# CSR8635-V1_2.net
KiCad netlist of a schematic drawn in EAGLE
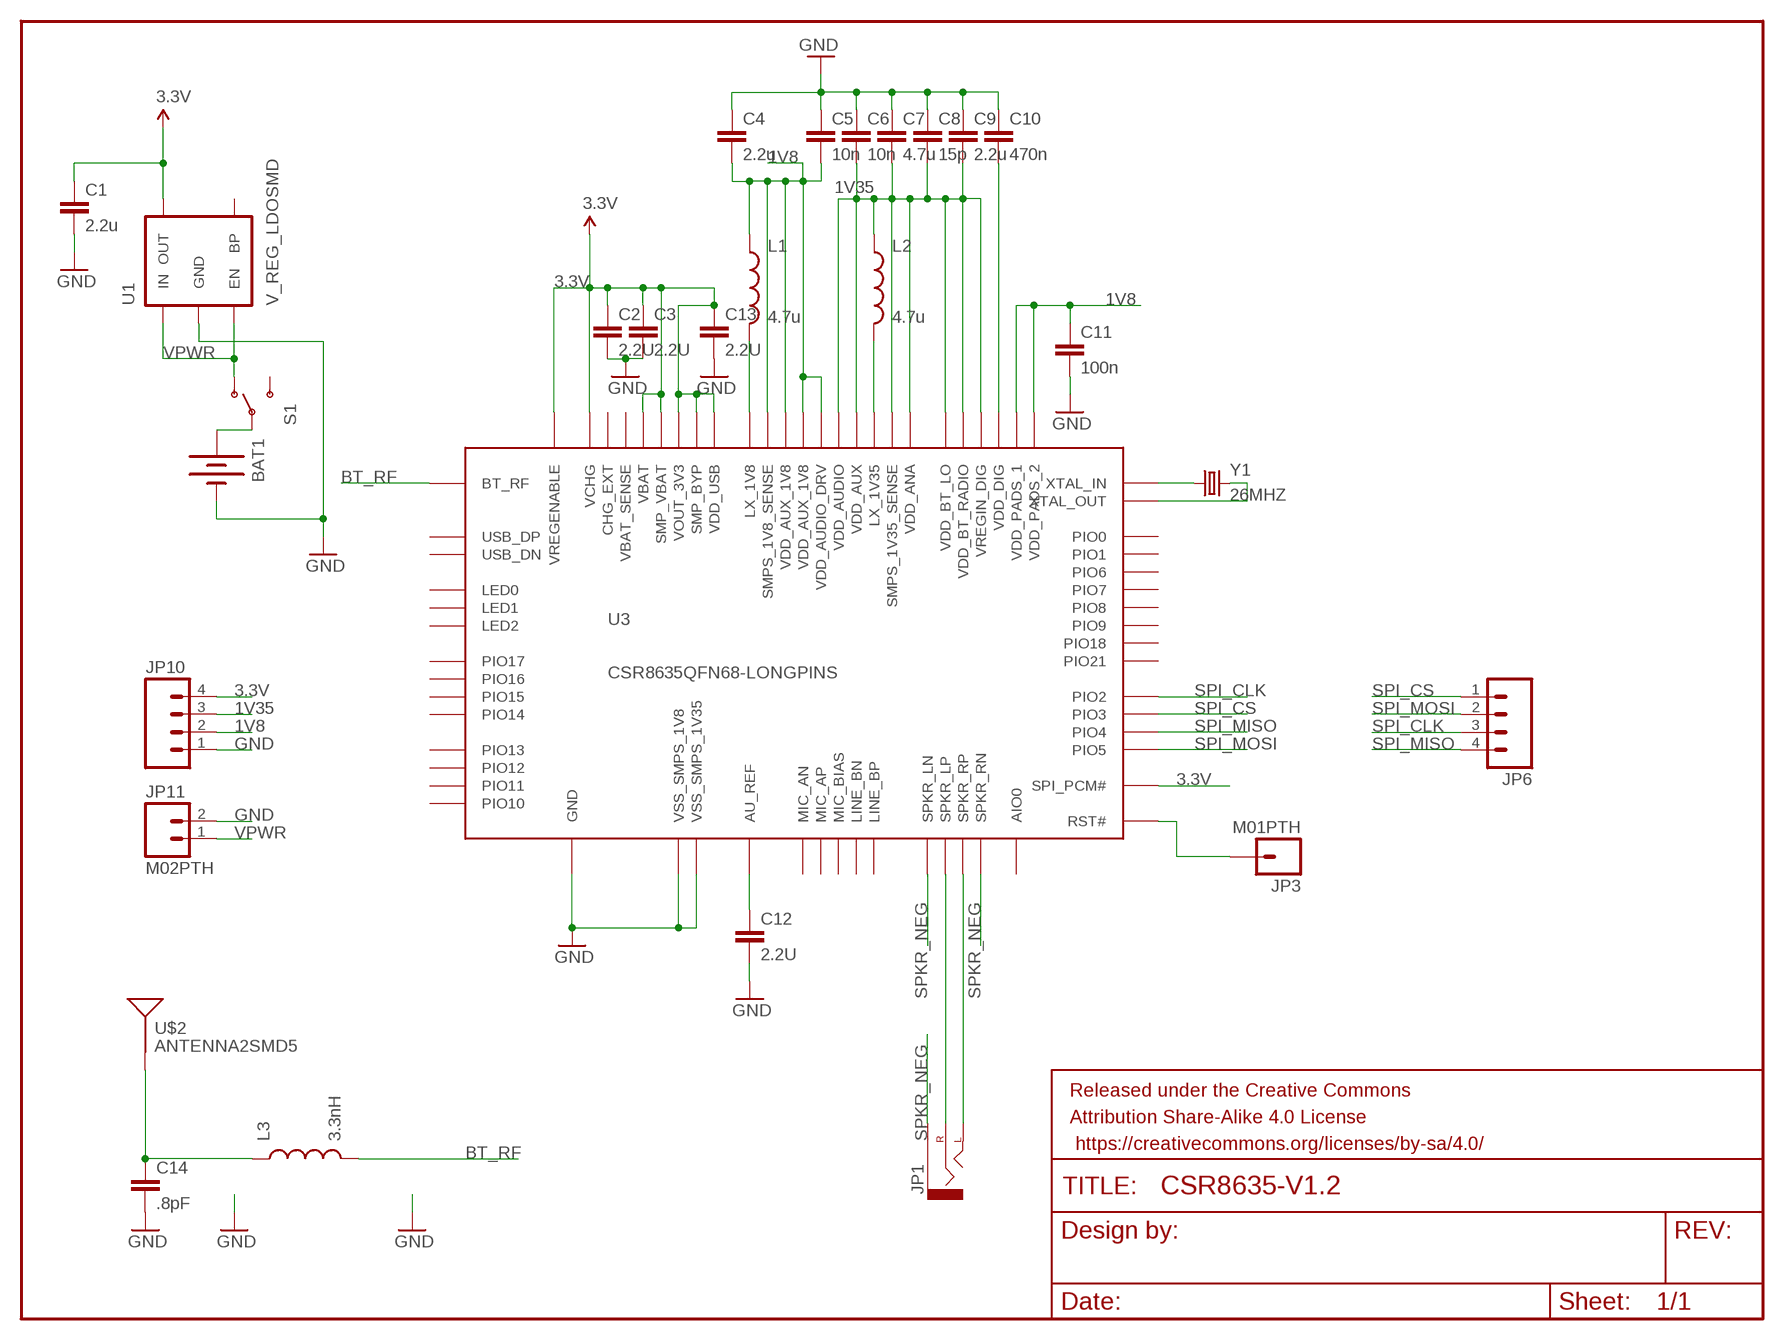
[diagram p0: schematic, sheet 1]

(export (version "E")
  (design (tool "Eeschema 10.0.6"))
  (components
    (comp (ref "BAT1")
      (value "BATTERY9V")
      (footprint "eagle-import:BATTCON_9V")
      (libsource (lib "eagle-import") (part "BATTERY9V"))
    )
    (comp (ref "C1")
      (value "2.2u")
      (footprint "eagle-import:0603-CAP")
      (libsource (lib "eagle-import") (part "CAP0603-CAP"))
    )
    (comp (ref "C2")
      (value "2.2U")
      (footprint "eagle-import:0603-CAP")
      (libsource (lib "eagle-import") (part "CAP0603-CAP"))
    )
    (comp (ref "C3")
      (value "2.2U")
      (footprint "eagle-import:0603-CAP")
      (libsource (lib "eagle-import") (part "CAP0603-CAP"))
    )
    (comp (ref "C4")
      (value "2.2u")
      (footprint "eagle-import:0603-CAP")
      (libsource (lib "eagle-import") (part "CAP0603-CAP"))
    )
    (comp (ref "C5")
      (value "10n")
      (footprint "eagle-import:0603-CAP")
      (libsource (lib "eagle-import") (part "CAP0603-CAP"))
    )
    (comp (ref "C6")
      (value "10n")
      (footprint "eagle-import:0603-CAP")
      (libsource (lib "eagle-import") (part "CAP0603-CAP"))
    )
    (comp (ref "C7")
      (value "4.7u")
      (footprint "eagle-import:0603-CAP")
      (libsource (lib "eagle-import") (part "CAP0603-CAP"))
    )
    (comp (ref "C8")
      (value "15p")
      (footprint "eagle-import:0603-CAP")
      (libsource (lib "eagle-import") (part "CAP0603-CAP"))
    )
    (comp (ref "C9")
      (value "2.2u")
      (footprint "eagle-import:0603-CAP")
      (libsource (lib "eagle-import") (part "CAP0603-CAP"))
    )
    (comp (ref "C10")
      (value "470n")
      (footprint "eagle-import:0603-CAP")
      (libsource (lib "eagle-import") (part "CAP0603-CAP"))
    )
    (comp (ref "C11")
      (value "100n")
      (footprint "eagle-import:0603-CAP")
      (libsource (lib "eagle-import") (part "CAP0603-CAP"))
    )
    (comp (ref "C12")
      (value "2.2U")
      (footprint "eagle-import:0603-CAP")
      (libsource (lib "eagle-import") (part "CAP0603-CAP"))
    )
    (comp (ref "C13")
      (value "2.2U")
      (footprint "eagle-import:0603-CAP")
      (libsource (lib "eagle-import") (part "CAP0603-CAP"))
    )
    (comp (ref "C14")
      (value ".8pF")
      (footprint "eagle-import:0603-CAP")
      (libsource (lib "eagle-import") (part "CAP0603-CAP"))
    )
    (comp (ref "FRAME1")
      (value "FRAME-LETTER")
      (footprint "eagle-import:CREATIVE_COMMONS")
      (libsource (lib "eagle-import") (part "FRAME-LETTER"))
    )
    (comp (ref "JP1")
      (value "AUDIO-JACKSMD2")
      (footprint "eagle-import:AUDIO-JACK-3.5MM-SMD")
      (libsource (lib "eagle-import") (part "AUDIO-JACKSMD2"))
    )
    (comp (ref "JP3")
      (value "M01PTH")
      (footprint "eagle-import:1X01")
      (libsource (lib "eagle-import") (part "M01PTH"))
    )
    (comp (ref "JP6")
      (value "M04PTH")
      (footprint "eagle-import:1X04")
      (libsource (lib "eagle-import") (part "M04PTH"))
    )
    (comp (ref "JP10")
      (value "M04PTH")
      (footprint "eagle-import:1X04")
      (libsource (lib "eagle-import") (part "M04PTH"))
    )
    (comp (ref "JP11")
      (value "M02PTH")
      (footprint "eagle-import:1X02")
      (libsource (lib "eagle-import") (part "M02PTH"))
    )
    (comp (ref "L1")
      (value "4.7u")
      (footprint "eagle-import:0805")
      (libsource (lib "eagle-import") (part "INDUCTOR0805"))
    )
    (comp (ref "L2")
      (value "4.7u")
      (footprint "eagle-import:0805")
      (libsource (lib "eagle-import") (part "INDUCTOR0805"))
    )
    (comp (ref "L3")
      (value "3.3nH")
      (footprint "eagle-import:0805")
      (libsource (lib "eagle-import") (part "INDUCTOR0805"))
    )
    (comp (ref "S1")
      (value "SWITCH-SPDTPTH")
      (footprint "eagle-import:SWITCH-SPDT")
      (libsource (lib "eagle-import") (part "SWITCH-SPDTPTH"))
    )
    (comp (ref "U$2")
      (value "ANTENNA2SMD5")
      (footprint "eagle-import:ANTENNA-CHIP5")
      (libsource (lib "eagle-import") (part "ANTENNA2SMD5"))
    )
    (comp (ref "U1")
      (value "V_REG_LDOSMD")
      (footprint "eagle-import:SOT23-5")
      (libsource (lib "eagle-import") (part "V_REG_LDOSMD"))
    )
    (comp (ref "U3")
      (value "CSR8635QFN68-LONGPINS")
      (footprint "eagle-import:QFN68")
      (libsource (lib "eagle-import") (part "CSR8635QFN68-LONGPINS"))
    )
    (comp (ref "Y1")
      (value "26MHZ")
      (footprint "eagle-import:HC49US")
      (libsource (lib "eagle-import") (part "CRYSTALHC49US"))
    )
  )
  (nets
    (net (code "1") (name "/1V8") (class "Default")
      (node (ref "C11") (pin "1") (pinfunction "1_1") (pintype "passive"))
      (node (ref "C4") (pin "2") (pinfunction "2_2") (pintype "passive"))
      (node (ref "C5") (pin "2") (pinfunction "2_2") (pintype "passive"))
      (node (ref "JP10") (pin "2") (pinfunction "2_2") (pintype "passive"))
      (node (ref "L1") (pin "1") (pinfunction "1_1") (pintype "passive"))
      (node (ref "U3") (pin "15") (pinfunction "VDD_AUX_1V8_15") (pintype "power_in"))
      (node (ref "U3") (pin "16") (pinfunction "VDD_AUX_1V8_16") (pintype "power_in"))
      (node (ref "U3") (pin "33") (pinfunction "VDD_PADS_1_33") (pintype "bidirectional"))
      (node (ref "U3") (pin "53") (pinfunction "SMPS_1V8_SENSE_53") (pintype "bidirectional"))
      (node (ref "U3") (pin "63") (pinfunction "VDD_PADS_2_63") (pintype "power_in"))
      (node (ref "U3") (pin "8") (pinfunction "VDD_AUDIO_DRV_8") (pintype "power_in"))
    )
    (net (code "2") (name "/1V35") (class "Default")
      (node (ref "C6") (pin "2") (pinfunction "2_2") (pintype "passive"))
      (node (ref "C7") (pin "2") (pinfunction "2_2") (pintype "passive"))
      (node (ref "C8") (pin "2") (pinfunction "2_2") (pintype "passive"))
      (node (ref "C9") (pin "2") (pinfunction "2_2") (pintype "passive"))
      (node (ref "JP10") (pin "3") (pinfunction "3_3") (pintype "passive"))
      (node (ref "L2") (pin "1") (pinfunction "1_1") (pintype "passive"))
      (node (ref "U3") (pin "11") (pinfunction "VDD_BT_RADIO_11") (pintype "power_in"))
      (node (ref "U3") (pin "13") (pinfunction "VDD_BT_LO_13") (pintype "power_in"))
      (node (ref "U3") (pin "14") (pinfunction "VDD_AUX_14") (pintype "power_in"))
      (node (ref "U3") (pin "17") (pinfunction "VDD_ANA_17") (pintype "power_in"))
      (node (ref "U3") (pin "3") (pinfunction "VDD_AUDIO_3") (pintype "power_in"))
      (node (ref "U3") (pin "39") (pinfunction "VREGIN_DIG_39") (pintype "bidirectional"))
      (node (ref "U3") (pin "52") (pinfunction "SMPS_1V35_SENSE_52") (pintype "bidirectional"))
    )
    (net (code "3") (name "/BT_RF") (class "Default")
      (node (ref "L3") (pin "2") (pinfunction "2_2") (pintype "passive"))
      (node (ref "U3") (pin "12") (pinfunction "BT_RF_12") (pintype "bidirectional"))
    )
    (net (code "4") (name "/SPI_CLK") (class "Default")
      (node (ref "JP6") (pin "3") (pinfunction "3_3") (pintype "passive"))
      (node (ref "U3") (pin "30") (pinfunction "PIO2_30") (pintype "bidirectional"))
    )
    (net (code "5") (name "/SPI_CS") (class "Default")
      (node (ref "JP6") (pin "1") (pinfunction "1_1") (pintype "passive"))
      (node (ref "U3") (pin "28") (pinfunction "PIO3_28") (pintype "bidirectional"))
    )
    (net (code "6") (name "/SPI_MISO") (class "Default")
      (node (ref "JP6") (pin "4") (pinfunction "4_4") (pintype "passive"))
      (node (ref "U3") (pin "24") (pinfunction "PIO4_24") (pintype "bidirectional"))
    )
    (net (code "7") (name "/SPI_MOSI") (class "Default")
      (node (ref "JP6") (pin "2") (pinfunction "2_2") (pintype "passive"))
      (node (ref "U3") (pin "34") (pinfunction "PIO5_34") (pintype "bidirectional"))
    )
    (net (code "8") (name "/SPKR_NEG") (class "Default")
      (node (ref "JP1") (pin "SLEEVE") (pinfunction "SLEEVE_SLEEVE") (pintype "bidirectional"))
      (node (ref "U3") (pin "6") (pinfunction "SPKR_RN_6") (pintype "bidirectional"))
      (node (ref "U3") (pin "9") (pinfunction "SPKR_LN_9") (pintype "bidirectional"))
    )
    (net (code "9") (name "/VPWR") (class "Default")
      (node (ref "JP11") (pin "1") (pinfunction "1_1") (pintype "passive"))
      (node (ref "S1") (pin "1") (pinfunction "O_1") (pintype "passive"))
      (node (ref "U1") (pin "1") (pinfunction "IN_1") (pintype "input"))
      (node (ref "U1") (pin "3") (pinfunction "EN_3") (pintype "input"))
    )
    (net (code "10") (name "3.3V") (class "Default")
      (node (ref "C1") (pin "1") (pinfunction "1_1") (pintype "passive"))
      (node (ref "C13") (pin "1") (pinfunction "1_1") (pintype "passive"))
      (node (ref "C2") (pin "1") (pinfunction "1_1") (pintype "passive"))
      (node (ref "C3") (pin "1") (pinfunction "1_1") (pintype "passive"))
      (node (ref "JP10") (pin "4") (pinfunction "4_4") (pintype "passive"))
      (node (ref "U1") (pin "5") (pinfunction "OUT_5") (pintype "passive"))
      (node (ref "U3") (pin "29") (pinfunction "SPI_PCM#_29") (pintype "bidirectional"))
      (node (ref "U3") (pin "40") (pinfunction "VREGENABLE_40") (pintype "bidirectional"))
      (node (ref "U3") (pin "41") (pinfunction "VOUT_3V3_41") (pintype "power_in"))
      (node (ref "U3") (pin "42") (pinfunction "VCHG_42") (pintype "bidirectional"))
      (node (ref "U3") (pin "45") (pinfunction "VBAT_45") (pintype "power_in"))
      (node (ref "U3") (pin "48") (pinfunction "SMP_VBAT_48") (pintype "bidirectional"))
      (node (ref "U3") (pin "49") (pinfunction "SMP_BYP_49") (pintype "bidirectional"))
      (node (ref "U3") (pin "54") (pinfunction "VDD_USB_54") (pintype "power_in"))
    )
    (net (code "11") (name "GND") (class "Default")
      (node (ref "BAT1") (pin "-") (pinfunction "-_-") (pintype "power_in"))
      (node (ref "C1") (pin "2") (pinfunction "2_2") (pintype "passive"))
      (node (ref "C10") (pin "1") (pinfunction "1_1") (pintype "passive"))
      (node (ref "C11") (pin "2") (pinfunction "2_2") (pintype "passive"))
      (node (ref "C12") (pin "2") (pinfunction "2_2") (pintype "passive"))
      (node (ref "C13") (pin "2") (pinfunction "2_2") (pintype "passive"))
      (node (ref "C14") (pin "2") (pinfunction "2_2") (pintype "passive"))
      (node (ref "C2") (pin "2") (pinfunction "2_2") (pintype "passive"))
      (node (ref "C3") (pin "2") (pinfunction "2_2") (pintype "passive"))
      (node (ref "C4") (pin "1") (pinfunction "1_1") (pintype "passive"))
      (node (ref "C5") (pin "1") (pinfunction "1_1") (pintype "passive"))
      (node (ref "C6") (pin "1") (pinfunction "1_1") (pintype "passive"))
      (node (ref "C7") (pin "1") (pinfunction "1_1") (pintype "passive"))
      (node (ref "C8") (pin "1") (pinfunction "1_1") (pintype "passive"))
      (node (ref "C9") (pin "1") (pinfunction "1_1") (pintype "passive"))
      (node (ref "JP10") (pin "1") (pinfunction "1_1") (pintype "passive"))
      (node (ref "JP11") (pin "2") (pinfunction "2_2") (pintype "passive"))
      (node (ref "U1") (pin "2") (pinfunction "GND_2") (pintype "input"))
      (node (ref "U3") (pin "46") (pinfunction "VSS_SMPS_1V8_46") (pintype "bidirectional"))
      (node (ref "U3") (pin "51") (pinfunction "VSS_SMPS_1V35_51") (pintype "bidirectional"))
      (node (ref "U3") (pin "CNTR") (pinfunction "GND_CNTR") (pintype "bidirectional"))
      (node (ref "U3") (pin "CNTR1") (pinfunction "GND_CNTR1") (pintype "bidirectional"))
      (node (ref "U3") (pin "CNTR2") (pinfunction "GND_CNTR2") (pintype "bidirectional"))
      (node (ref "U3") (pin "CNTR3") (pinfunction "GND_CNTR3") (pintype "bidirectional"))
    )
    (net (code "12") (name "Net-(JP1-LEFT)") (class "Default")
      (node (ref "JP1") (pin "TIP") (pinfunction "LEFT_TIP") (pintype "bidirectional"))
      (node (ref "U3") (pin "7") (pinfunction "SPKR_RP_7") (pintype "bidirectional"))
    )
    (net (code "13") (name "Net-(JP1-RIGHT)") (class "Default")
      (node (ref "JP1") (pin "RING") (pinfunction "RIGHT_RING") (pintype "bidirectional"))
      (node (ref "U3") (pin "10") (pinfunction "SPKR_LP_10") (pintype "bidirectional"))
    )
    (net (code "14") (name "Net-(S1-P)") (class "Default")
      (node (ref "BAT1") (pin "+") (pinfunction "+_+") (pintype "power_in"))
      (node (ref "S1") (pin "2") (pinfunction "P_2") (pintype "passive"))
    )
    (net (code "15") (name "Net-(U$2-SIGNAL)") (class "Default")
      (node (ref "C14") (pin "1") (pinfunction "1_1") (pintype "passive"))
      (node (ref "L3") (pin "1") (pinfunction "1_1") (pintype "passive"))
      (node (ref "U$2") (pin "FEED") (pinfunction "SIGNAL_FEED") (pintype "bidirectional"))
    )
    (net (code "16") (name "Net-(U3-AU_REF)") (class "Default")
      (node (ref "C12") (pin "1") (pinfunction "1_1") (pintype "passive"))
      (node (ref "U3") (pin "1") (pinfunction "AU_REF_1") (pintype "bidirectional"))
    )
    (net (code "17") (name "Net-(U3-LX_1V8)") (class "Default")
      (node (ref "L1") (pin "2") (pinfunction "2_2") (pintype "passive"))
      (node (ref "U3") (pin "47") (pinfunction "LX_1V8_47") (pintype "bidirectional"))
    )
    (net (code "18") (name "Net-(U3-LX_1V35)") (class "Default")
      (node (ref "L2") (pin "2") (pinfunction "2_2") (pintype "passive"))
      (node (ref "U3") (pin "50") (pinfunction "LX_1V35_50") (pintype "bidirectional"))
    )
    (net (code "19") (name "Net-(U3-RST#)") (class "Default")
      (node (ref "JP3") (pin "1") (pinfunction "1_1") (pintype "passive"))
      (node (ref "U3") (pin "35") (pinfunction "RST#_35") (pintype "bidirectional"))
    )
    (net (code "20") (name "Net-(U3-VDD_DIG)") (class "Default")
      (node (ref "C10") (pin "2") (pinfunction "2_2") (pintype "passive"))
      (node (ref "U3") (pin "38") (pinfunction "VDD_DIG_38") (pintype "power_in"))
    )
    (net (code "21") (name "Net-(U3-XTAL_IN)") (class "Default")
      (node (ref "U3") (pin "19") (pinfunction "XTAL_IN_19") (pintype "bidirectional"))
      (node (ref "Y1") (pin "1") (pinfunction "1_1") (pintype "passive"))
    )
    (net (code "22") (name "Net-(U3-XTAL_OUT)") (class "Default")
      (node (ref "U3") (pin "18") (pinfunction "XTAL_OUT_18") (pintype "bidirectional"))
      (node (ref "Y1") (pin "2") (pinfunction "2_2") (pintype "passive"))
    )
    (net (code "23") (name "unconnected-(S1-S-Pad3)") (class "Default")
      (node (ref "S1") (pin "3") (pinfunction "S_3") (pintype "passive"))
    )
    (net (code "24") (name "unconnected-(U1-BP-Pad4)") (class "Default")
      (node (ref "U1") (pin "4") (pinfunction "BP_4") (pintype "input"))
    )
    (net (code "25") (name "unconnected-(U3-AIO0-Pad20)") (class "Default")
      (node (ref "U3") (pin "20") (pinfunction "AIO0_20") (pintype "bidirectional"))
    )
    (net (code "26") (name "unconnected-(U3-CHG_EXT-Pad43)") (class "Default")
      (node (ref "U3") (pin "43") (pinfunction "CHG_EXT_43") (pintype "bidirectional"))
    )
    (net (code "27") (name "unconnected-(U3-LED0-Pad37)") (class "Default")
      (node (ref "U3") (pin "37") (pinfunction "LED0_37") (pintype "bidirectional"))
    )
    (net (code "28") (name "unconnected-(U3-LED1-Pad36)") (class "Default")
      (node (ref "U3") (pin "36") (pinfunction "LED1_36") (pintype "bidirectional"))
    )
    (net (code "29") (name "unconnected-(U3-LED2-Pad66)") (class "Default")
      (node (ref "U3") (pin "66") (pinfunction "LED2_66") (pintype "bidirectional"))
    )
    (net (code "30") (name "unconnected-(U3-LINE_BN-Pad4)") (class "Default")
      (node (ref "U3") (pin "4") (pinfunction "LINE_BN_4") (pintype "bidirectional"))
    )
    (net (code "31") (name "unconnected-(U3-LINE_BP-Pad5)") (class "Default")
      (node (ref "U3") (pin "5") (pinfunction "LINE_BP_5") (pintype "bidirectional"))
    )
    (net (code "32") (name "unconnected-(U3-MIC_AN-Pad67)") (class "Default")
      (node (ref "U3") (pin "67") (pinfunction "MIC_AN_67") (pintype "bidirectional"))
    )
    (net (code "33") (name "unconnected-(U3-MIC_AP-Pad68)") (class "Default")
      (node (ref "U3") (pin "68") (pinfunction "MIC_AP_68") (pintype "bidirectional"))
    )
    (net (code "34") (name "unconnected-(U3-MIC_BIAS-Pad2)") (class "Default")
      (node (ref "U3") (pin "2") (pinfunction "MIC_BIAS_2") (pintype "bidirectional"))
    )
    (net (code "35") (name "unconnected-(U3-PIO0-Pad59)") (class "Default")
      (node (ref "U3") (pin "59") (pinfunction "PIO0_59") (pintype "bidirectional"))
    )
    (net (code "36") (name "unconnected-(U3-PIO1-Pad60)") (class "Default")
      (node (ref "U3") (pin "60") (pinfunction "PIO1_60") (pintype "bidirectional"))
    )
    (net (code "37") (name "unconnected-(U3-PIO6-Pad62)") (class "Default")
      (node (ref "U3") (pin "62") (pinfunction "PIO6_62") (pintype "bidirectional"))
    )
    (net (code "38") (name "unconnected-(U3-PIO7-Pad57)") (class "Default")
      (node (ref "U3") (pin "57") (pinfunction "PIO7_57") (pintype "bidirectional"))
    )
    (net (code "39") (name "unconnected-(U3-PIO8-Pad61)") (class "Default")
      (node (ref "U3") (pin "61") (pinfunction "PIO8_61") (pintype "bidirectional"))
    )
    (net (code "40") (name "unconnected-(U3-PIO9-Pad58)") (class "Default")
      (node (ref "U3") (pin "58") (pinfunction "PIO9_58") (pintype "bidirectional"))
    )
    (net (code "41") (name "unconnected-(U3-PIO10-Pad25)") (class "Default")
      (node (ref "U3") (pin "25") (pinfunction "PIO10_25") (pintype "bidirectional"))
    )
    (net (code "42") (name "unconnected-(U3-PIO11-Pad26)") (class "Default")
      (node (ref "U3") (pin "26") (pinfunction "PIO11_26") (pintype "bidirectional"))
    )
    (net (code "43") (name "unconnected-(U3-PIO12-Pad22)") (class "Default")
      (node (ref "U3") (pin "22") (pinfunction "PIO12_22") (pintype "bidirectional"))
    )
    (net (code "44") (name "unconnected-(U3-PIO13-Pad31)") (class "Default")
      (node (ref "U3") (pin "31") (pinfunction "PIO13_31") (pintype "bidirectional"))
    )
    (net (code "45") (name "unconnected-(U3-PIO14-Pad23)") (class "Default")
      (node (ref "U3") (pin "23") (pinfunction "PIO14_23") (pintype "bidirectional"))
    )
    (net (code "46") (name "unconnected-(U3-PIO15-Pad21)") (class "Default")
      (node (ref "U3") (pin "21") (pinfunction "PIO15_21") (pintype "bidirectional"))
    )
    (net (code "47") (name "unconnected-(U3-PIO16-Pad27)") (class "Default")
      (node (ref "U3") (pin "27") (pinfunction "PIO16_27") (pintype "bidirectional"))
    )
    (net (code "48") (name "unconnected-(U3-PIO17-Pad32)") (class "Default")
      (node (ref "U3") (pin "32") (pinfunction "PIO17_32") (pintype "bidirectional"))
    )
    (net (code "49") (name "unconnected-(U3-PIO18-Pad65)") (class "Default")
      (node (ref "U3") (pin "65") (pinfunction "PIO18_65") (pintype "bidirectional"))
    )
    (net (code "50") (name "unconnected-(U3-PIO21-Pad64)") (class "Default")
      (node (ref "U3") (pin "64") (pinfunction "PIO21_64") (pintype "bidirectional"))
    )
    (net (code "51") (name "unconnected-(U3-USB_DN-Pad55)") (class "Default")
      (node (ref "U3") (pin "55") (pinfunction "USB_DN_55") (pintype "bidirectional"))
    )
    (net (code "52") (name "unconnected-(U3-USB_DP-Pad56)") (class "Default")
      (node (ref "U3") (pin "56") (pinfunction "USB_DP_56") (pintype "bidirectional"))
    )
    (net (code "53") (name "unconnected-(U3-VBAT_SENSE-Pad44)") (class "Default")
      (node (ref "U3") (pin "44") (pinfunction "VBAT_SENSE_44") (pintype "bidirectional"))
    )
  )
)
